# Connectors_GPIOs.net
KiCad netlist of a schematic drawn in Altium Designer
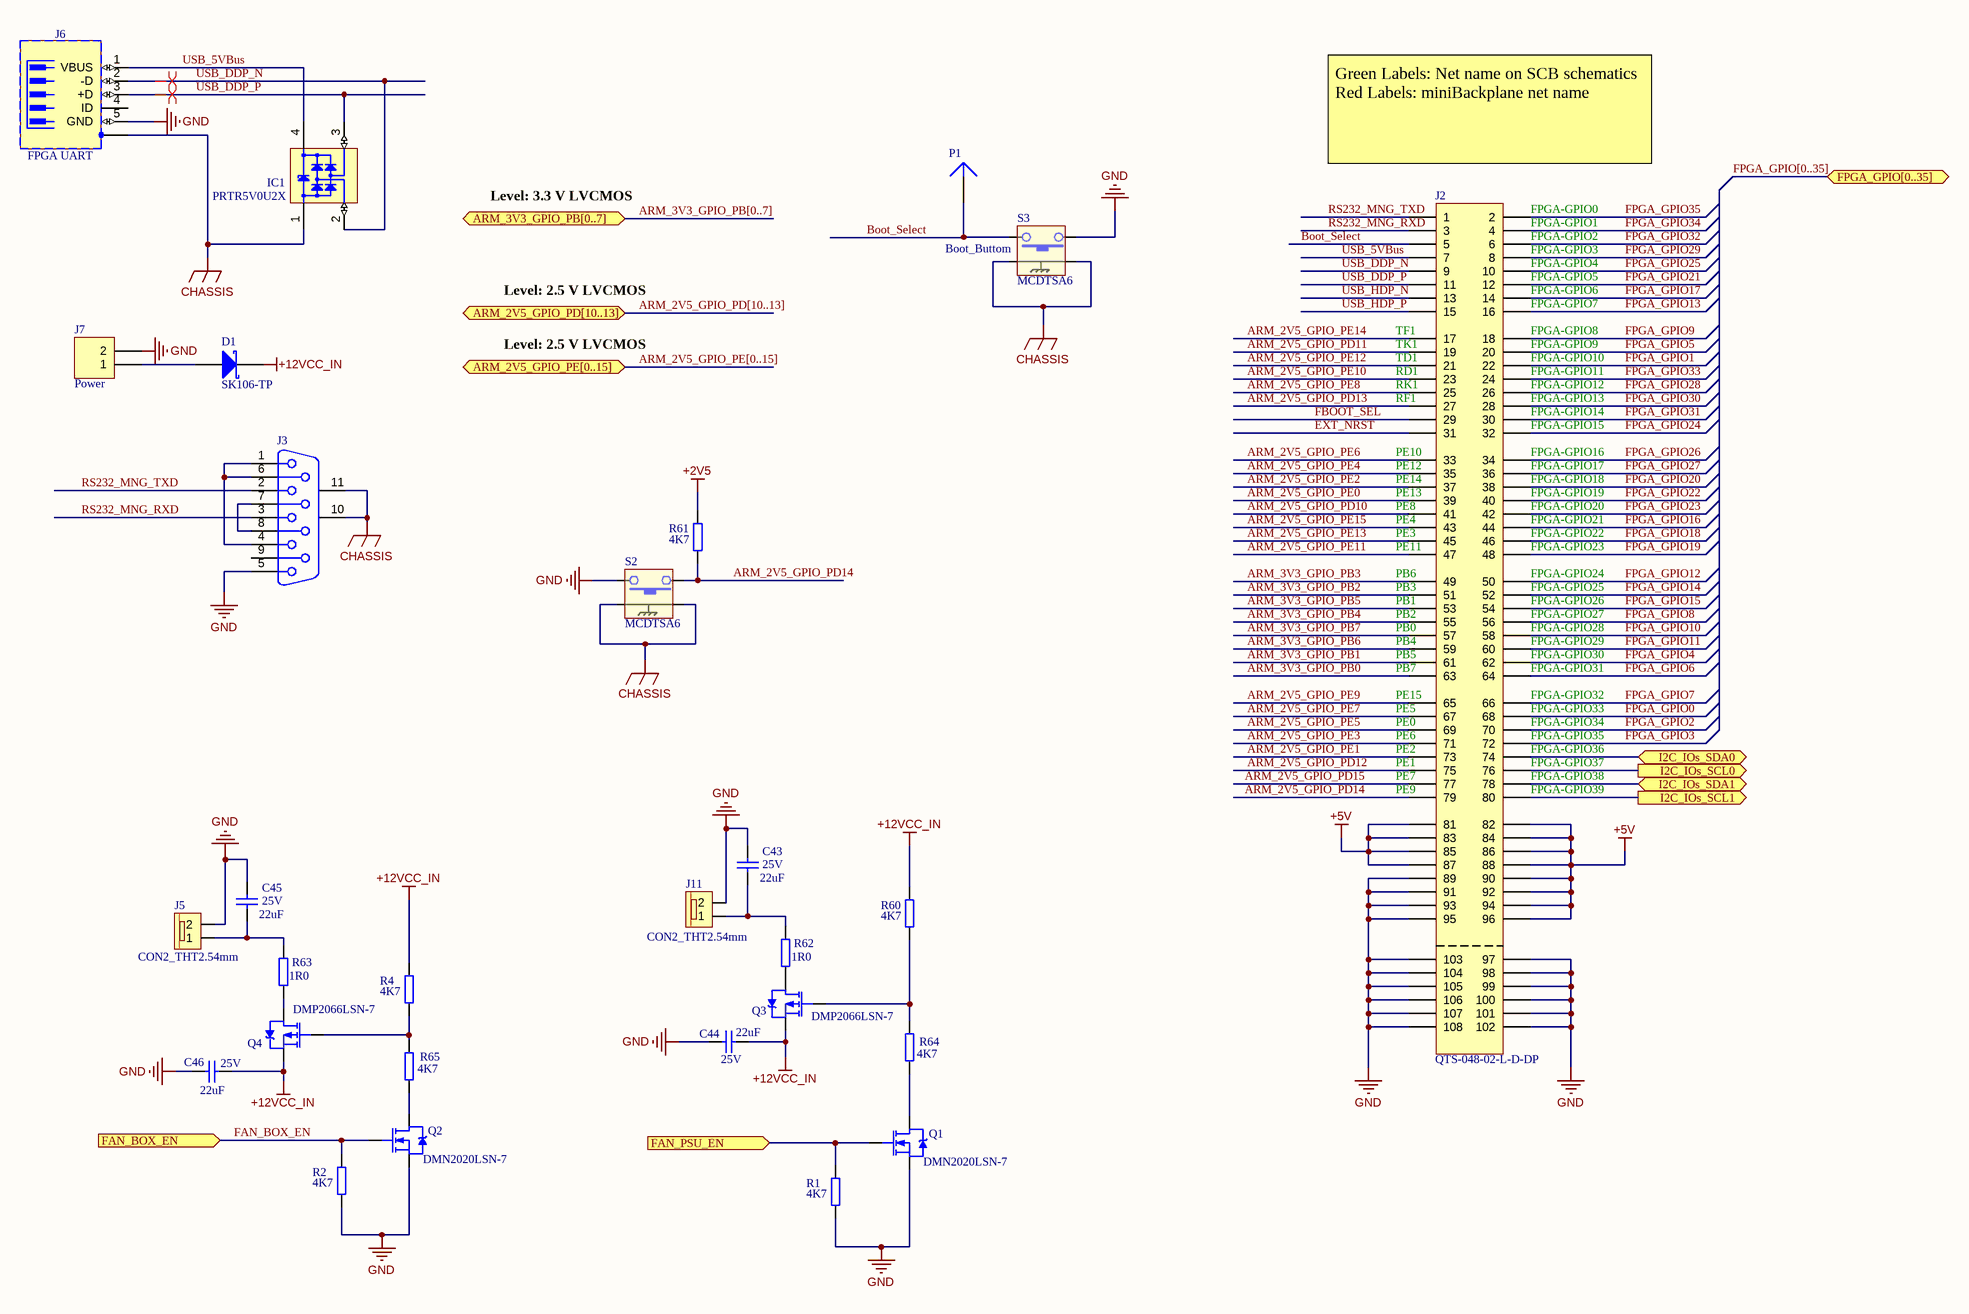
[diagram p0: Connectors_GPIOs.SchDoc]

(export (version "E")
  (design (tool "Eeschema 10.0.6"))
  (components
    (comp (ref "C43")
      (value "22uF")
      (footprint "CC3216-1206")
      (description "Capacitor")
      (fields
        (field (name "TOLERANCE") "±10%")
        (field (name "VOLTAGE") "25V")
        (field (name "Comment") "22uF 25V")
        (field (name "PUBLISHER") "Altium Limited")
      )
      (libsource (lib "wr_switch") (part "Cap"))
    )
    (comp (ref "C44")
      (value "22uF")
      (footprint "CC3216-1206")
      (description "Capacitor")
      (fields
        (field (name "TOLERANCE") "±10%")
        (field (name "VOLTAGE") "25V")
        (field (name "Comment") "22uF 25V")
        (field (name "PUBLISHER") "Altium Limited")
      )
      (libsource (lib "wr_switch") (part "Cap"))
    )
    (comp (ref "C45")
      (value "22uF")
      (footprint "CC3216-1206")
      (description "Capacitor")
      (fields
        (field (name "TOLERANCE") "±10%")
        (field (name "VOLTAGE") "25V")
        (field (name "Comment") "22uF 25V")
        (field (name "PUBLISHER") "Altium Limited")
      )
      (libsource (lib "wr_switch") (part "Cap"))
    )
    (comp (ref "C46")
      (value "22uF")
      (footprint "CC3216-1206")
      (description "Capacitor")
      (fields
        (field (name "TOLERANCE") "±10%")
        (field (name "VOLTAGE") "25V")
        (field (name "Comment") "22uF 25V")
        (field (name "PUBLISHER") "Altium Limited")
      )
      (libsource (lib "wr_switch") (part "Cap"))
    )
    (comp (ref "D1")
      (value "SK106-TP")
      (footprint "7S_WR:DO-214AB/SMB-MCC")
      (description "Schottky Diode 10A 60V")
      (libsource (lib "wr_switch") (part "SK106-TP"))
    )
    (comp (ref "IC1")
      (value "PRTR5V0U2X")
      (footprint "7S_WR:SOT190P230X110-4N")
      (description "Ultra Low Capacitance Double Rail-to-Rail ESD Protection Diode")
      (fields
        (field (name "VOLTAGE") "5.5V")
        (field (name "MANUFACTURER") "PHILIPS NXP")
        (field (name "AUTHOR") "CERN DEM JLC")
      )
      (libsource (lib "wr_switch") (part "PRTR5V0U2X"))
    )
    (comp (ref "J2")
      (value "QTS-048-02-L-D-DP")
      (footprint "QTS-048-XX-X-D-DP-A")
      (description "High Speed Ground Plane Header")
      (libsource (lib "wr_switch") (part "QTS-048-01-L-D-DP"))
    )
    (comp (ref "J3")
      (value "D Connector 9")
      (footprint "7S_WR:DSUB1.385-2H9")
      (description "Receptacle Assembly, 9 Position, Right Angle")
      (fields (field (name "PUBLISHER") "Altium Limited"))
      (libsource (lib "Miscellaneous Connectors") (part "D Connector 9"))
    )
    (comp (ref "J5")
      (value "CON2_THT2.54mm")
      (footprint "Wurth_619_0xx")
      (description "Connector")
      (libsource (lib "wr_switch") (part "CON2_619_0xx"))
    )
    (comp (ref "J6")
      (value "FPGA UART")
      (footprint "7S_WR:TYCO_1734035-1")
      (description "5 Pin + 1 Shield USB Receptacle")
      (fields
        (field (name "PART NUMBER") "TYCO_1734035-1")
        (field (name "MANUFACTURER") "TYCO ELECTRONICS")
        (field (name "AUTHOR") "CERN DEM JLC")
      )
      (libsource (lib "Connectors") (part "Connector USB 5 Pin + 1Shield"))
    )
    (comp (ref "J7")
      (value "Power")
      (footprint "7S_WR:TYCO_794120_1")
      (description "Header, 2-Pin")
      (fields (field (name "PUBLISHER") "Altium Limited"))
      (libsource (lib "Miscellaneous Connectors") (part "Header 2"))
    )
    (comp (ref "J11")
      (value "CON2_THT2.54mm")
      (footprint "Wurth_619_0xx")
      (description "Connector")
      (libsource (lib "wr_switch") (part "CON2_619_0xx"))
    )
    (comp (ref "P1")
      (value "Boot_Buttom")
      (footprint "PIN1-RT-01T-1.0B(LF)")
      (description "Plug")
      (fields (field (name "PUBLISHER") "Altium Limited"))
      (libsource (lib "Miscellaneous Connectors") (part "Plug"))
    )
    (comp (ref "Q1")
      (value "DMN2020LSN-7")
      (footprint "7S_WR:SC-59-3")
      (description "N-Channel Power MOSFET")
      (fields (field (name "MANUFACTURER") "Diodes Inc.") (field (name "PUBLISHER") "Altium Limited"))
      (libsource (lib "wr_switch") (part "NMOS-2"))
    )
    (comp (ref "Q2")
      (value "DMN2020LSN-7")
      (footprint "7S_WR:SC-59-3")
      (description "N-Channel Power MOSFET")
      (fields (field (name "MANUFACTURER") "Diodes Inc.") (field (name "PUBLISHER") "Altium Limited"))
      (libsource (lib "wr_switch") (part "NMOS-2"))
    )
    (comp (ref "Q3")
      (value "DMP2066LSN-7")
      (footprint "SC-59-3")
      (description "P-Channel Enhancement MOSFET")
      (fields (field (name "MANUFACTURER") "Diodes Inc."))
      (libsource (lib "wr_switch") (part "PMOS-2-Reflexion"))
    )
    (comp (ref "Q4")
      (value "DMP2066LSN-7")
      (footprint "SC-59-3")
      (description "P-Channel Enhancement MOSFET")
      (fields (field (name "MANUFACTURER") "Diodes Inc."))
      (libsource (lib "wr_switch") (part "PMOS-2-Reflexion"))
    )
    (comp (ref "R1")
      (value "4K7")
      (footprint "0603")
      (description "SMD Resistor")
      (fields (field (name "TOLERANCE") "±1%"))
      (libsource (lib "wr_switch") (part "RES_SMD"))
    )
    (comp (ref "R2")
      (value "4K7")
      (footprint "0603")
      (description "SMD Resistor")
      (fields (field (name "TOLERANCE") "±1%"))
      (libsource (lib "wr_switch") (part "RES_SMD"))
    )
    (comp (ref "R4")
      (value "4K7")
      (footprint "0603")
      (description "SMD Resistor")
      (fields (field (name "TOLERANCE") "±1%"))
      (libsource (lib "wr_switch") (part "RES_SMD"))
    )
    (comp (ref "R60")
      (value "4K7")
      (footprint "0603")
      (description "SMD Resistor")
      (fields (field (name "TOLERANCE") "±1%"))
      (libsource (lib "wr_switch") (part "RES_SMD"))
    )
    (comp (ref "R61")
      (value "4K7")
      (footprint "0603")
      (description "SMD Resistor")
      (fields (field (name "TOLERANCE") "±1%"))
      (libsource (lib "wr_switch") (part "RES_SMD"))
    )
    (comp (ref "R62")
      (value "1R0")
      (footprint "CR3225-1210")
      (description "SMD Resistor")
      (fields (field (name "TOLERANCE") "±1%"))
      (libsource (lib "wr_switch") (part "RES_SMD"))
    )
    (comp (ref "R63")
      (value "1R0")
      (footprint "CR3225-1210")
      (description "SMD Resistor")
      (fields (field (name "TOLERANCE") "±1%"))
      (libsource (lib "wr_switch") (part "RES_SMD"))
    )
    (comp (ref "R64")
      (value "4K7")
      (footprint "0603")
      (description "SMD Resistor")
      (fields (field (name "TOLERANCE") "±1%"))
      (libsource (lib "wr_switch") (part "RES_SMD"))
    )
    (comp (ref "R65")
      (value "4K7")
      (footprint "0603")
      (description "SMD Resistor")
      (fields (field (name "TOLERANCE") "±1%"))
      (libsource (lib "wr_switch") (part "RES_SMD"))
    )
    (comp (ref "S2")
      (value "MCDTSA6")
      (footprint "MCDTSA6")
      (description "Push button SPNO Right Angle Through Hole")
      (libsource (lib "wr_switch") (part "MCDTSA6"))
    )
    (comp (ref "S3")
      (value "MCDTSA6")
      (footprint "MCDTSA6")
      (description "Push button SPNO Right Angle Through Hole")
      (libsource (lib "wr_switch") (part "MCDTSA6"))
    )
  )
  (nets
    (net (code "1") (name "+2V5") (class "Default")
      (node (ref "R61") (pin "1") (pinfunction "1_1") (pintype "passive"))
    )
    (net (code "2") (name "+5V") (class "Default")
      (node (ref "J2") (pin "81") (pinfunction "81_81") (pintype "passive"))
      (node (ref "J2") (pin "82") (pinfunction "82_82") (pintype "passive"))
      (node (ref "J2") (pin "83") (pinfunction "83_83") (pintype "passive"))
      (node (ref "J2") (pin "84") (pinfunction "84_84") (pintype "passive"))
      (node (ref "J2") (pin "85") (pinfunction "85_85") (pintype "passive"))
      (node (ref "J2") (pin "86") (pinfunction "86_86") (pintype "passive"))
      (node (ref "J2") (pin "87") (pinfunction "87_87") (pintype "passive"))
      (node (ref "J2") (pin "88") (pinfunction "88_88") (pintype "passive"))
      (node (ref "J2") (pin "90") (pinfunction "90_90") (pintype "passive"))
      (node (ref "J2") (pin "92") (pinfunction "92_92") (pintype "passive"))
      (node (ref "J2") (pin "94") (pinfunction "94_94") (pintype "passive"))
      (node (ref "J2") (pin "96") (pinfunction "96_96") (pintype "passive"))
    )
    (net (code "3") (name "+12VCC_IN") (class "Default")
      (node (ref "C44") (pin "1") (pinfunction "1_1") (pintype "passive"))
      (node (ref "C46") (pin "1") (pinfunction "1_1") (pintype "passive"))
      (node (ref "D1") (pin "1") (pinfunction "K_1") (pintype "passive"))
      (node (ref "Q3") (pin "3") (pinfunction "S_3") (pintype "passive"))
      (node (ref "Q4") (pin "3") (pinfunction "S_3") (pintype "passive"))
      (node (ref "R4") (pin "1") (pinfunction "1_1") (pintype "passive"))
      (node (ref "R60") (pin "1") (pinfunction "1_1") (pintype "passive"))
    )
    (net (code "4") (name "/ARM_2V5_GPIO_PD10") (class "Default")
      (node (ref "J2") (pin "41") (pinfunction "41_41") (pintype "passive"))
    )
    (net (code "5") (name "/ARM_2V5_GPIO_PD11") (class "Default")
      (node (ref "J2") (pin "19") (pinfunction "19_19") (pintype "passive"))
    )
    (net (code "6") (name "/ARM_2V5_GPIO_PD12") (class "Default")
      (node (ref "J2") (pin "75") (pinfunction "75_75") (pintype "passive"))
    )
    (net (code "7") (name "/ARM_2V5_GPIO_PD13") (class "Default")
      (node (ref "J2") (pin "27") (pinfunction "27_27") (pintype "passive"))
    )
    (net (code "8") (name "/ARM_2V5_GPIO_PD14") (class "Default")
      (node (ref "J2") (pin "79") (pinfunction "79_79") (pintype "passive"))
      (node (ref "R61") (pin "2") (pinfunction "2_2") (pintype "passive"))
      (node (ref "S2") (pin "1") (pinfunction "1_1") (pintype "passive"))
    )
    (net (code "9") (name "/ARM_2V5_GPIO_PD15") (class "Default")
      (node (ref "J2") (pin "77") (pinfunction "77_77") (pintype "passive"))
    )
    (net (code "11") (name "/ARM_2V5_GPIO_PE0") (class "Default")
      (node (ref "J2") (pin "39") (pinfunction "39_39") (pintype "passive"))
    )
    (net (code "12") (name "/ARM_2V5_GPIO_PE1") (class "Default")
      (node (ref "J2") (pin "73") (pinfunction "73_73") (pintype "passive"))
    )
    (net (code "13") (name "/ARM_2V5_GPIO_PE2") (class "Default")
      (node (ref "J2") (pin "37") (pinfunction "37_37") (pintype "passive"))
    )
    (net (code "14") (name "/ARM_2V5_GPIO_PE3") (class "Default")
      (node (ref "J2") (pin "71") (pinfunction "71_71") (pintype "passive"))
    )
    (net (code "15") (name "/ARM_2V5_GPIO_PE4") (class "Default")
      (node (ref "J2") (pin "35") (pinfunction "35_35") (pintype "passive"))
    )
    (net (code "16") (name "/ARM_2V5_GPIO_PE5") (class "Default")
      (node (ref "J2") (pin "69") (pinfunction "69_69") (pintype "passive"))
    )
    (net (code "17") (name "/ARM_2V5_GPIO_PE6") (class "Default")
      (node (ref "J2") (pin "33") (pinfunction "33_33") (pintype "passive"))
    )
    (net (code "18") (name "/ARM_2V5_GPIO_PE7") (class "Default")
      (node (ref "J2") (pin "67") (pinfunction "67_67") (pintype "passive"))
    )
    (net (code "19") (name "/ARM_2V5_GPIO_PE8") (class "Default")
      (node (ref "J2") (pin "25") (pinfunction "25_25") (pintype "passive"))
    )
    (net (code "20") (name "/ARM_2V5_GPIO_PE9") (class "Default")
      (node (ref "J2") (pin "65") (pinfunction "65_65") (pintype "passive"))
    )
    (net (code "21") (name "/ARM_2V5_GPIO_PE10") (class "Default")
      (node (ref "J2") (pin "23") (pinfunction "23_23") (pintype "passive"))
    )
    (net (code "22") (name "/ARM_2V5_GPIO_PE11") (class "Default")
      (node (ref "J2") (pin "47") (pinfunction "47_47") (pintype "passive"))
    )
    (net (code "23") (name "/ARM_2V5_GPIO_PE12") (class "Default")
      (node (ref "J2") (pin "21") (pinfunction "21_21") (pintype "passive"))
    )
    (net (code "24") (name "/ARM_2V5_GPIO_PE13") (class "Default")
      (node (ref "J2") (pin "45") (pinfunction "45_45") (pintype "passive"))
    )
    (net (code "25") (name "/ARM_2V5_GPIO_PE14") (class "Default")
      (node (ref "J2") (pin "17") (pinfunction "17_17") (pintype "passive"))
    )
    (net (code "26") (name "/ARM_2V5_GPIO_PE15") (class "Default")
      (node (ref "J2") (pin "43") (pinfunction "43_43") (pintype "passive"))
    )
    (net (code "28") (name "/ARM_3V3_GPIO_PB0") (class "Default")
      (node (ref "J2") (pin "63") (pinfunction "63_63") (pintype "passive"))
    )
    (net (code "29") (name "/ARM_3V3_GPIO_PB1") (class "Default")
      (node (ref "J2") (pin "61") (pinfunction "61_61") (pintype "passive"))
    )
    (net (code "30") (name "/ARM_3V3_GPIO_PB2") (class "Default")
      (node (ref "J2") (pin "51") (pinfunction "51_51") (pintype "passive"))
    )
    (net (code "31") (name "/ARM_3V3_GPIO_PB3") (class "Default")
      (node (ref "J2") (pin "49") (pinfunction "49_49") (pintype "passive"))
    )
    (net (code "32") (name "/ARM_3V3_GPIO_PB4") (class "Default")
      (node (ref "J2") (pin "55") (pinfunction "55_55") (pintype "passive"))
    )
    (net (code "33") (name "/ARM_3V3_GPIO_PB5") (class "Default")
      (node (ref "J2") (pin "53") (pinfunction "53_53") (pintype "passive"))
    )
    (net (code "34") (name "/ARM_3V3_GPIO_PB6") (class "Default")
      (node (ref "J2") (pin "59") (pinfunction "59_59") (pintype "passive"))
    )
    (net (code "35") (name "/ARM_3V3_GPIO_PB7") (class "Default")
      (node (ref "J2") (pin "57") (pinfunction "57_57") (pintype "passive"))
    )
    (net (code "37") (name "/Boot_Select") (class "Default")
      (node (ref "J2") (pin "5") (pinfunction "5_5") (pintype "passive"))
      (node (ref "P1") (pin "1") (pinfunction "1_1") (pintype "passive"))
      (node (ref "S3") (pin "2") (pinfunction "2_2") (pintype "passive"))
    )
    (net (code "38") (name "/EXT_NRST") (class "Default")
      (node (ref "J2") (pin "31") (pinfunction "31_31") (pintype "passive"))
    )
    (net (code "39") (name "/FAN_BOX_EN") (class "Default")
      (node (ref "Q2") (pin "1") (pinfunction "G_1") (pintype "passive"))
      (node (ref "R2") (pin "1") (pinfunction "1_1") (pintype "passive"))
    )
    (net (code "40") (name "/FAN_PSU_EN") (class "Default")
      (node (ref "Q1") (pin "1") (pinfunction "G_1") (pintype "passive"))
      (node (ref "R1") (pin "1") (pinfunction "1_1") (pintype "passive"))
    )
    (net (code "41") (name "/FBOOT_SEL") (class "Default")
      (node (ref "J2") (pin "29") (pinfunction "29_29") (pintype "passive"))
    )
    (net (code "42") (name "/FPGA-GPIO36") (class "Default")
      (node (ref "J2") (pin "74") (pinfunction "74_74") (pintype "passive"))
    )
    (net (code "43") (name "/FPGA-GPIO37") (class "Default")
      (node (ref "J2") (pin "76") (pinfunction "76_76") (pintype "passive"))
    )
    (net (code "44") (name "/FPGA-GPIO38") (class "Default")
      (node (ref "J2") (pin "78") (pinfunction "78_78") (pintype "passive"))
    )
    (net (code "45") (name "/FPGA-GPIO39") (class "Default")
      (node (ref "J2") (pin "80") (pinfunction "80_80") (pintype "passive"))
    )
    (net (code "46") (name "/FPGA_GPIO0") (class "Default")
      (node (ref "J2") (pin "68") (pinfunction "68_68") (pintype "passive"))
    )
    (net (code "47") (name "/FPGA_GPIO1") (class "Default")
      (node (ref "J2") (pin "22") (pinfunction "22_22") (pintype "passive"))
    )
    (net (code "48") (name "/FPGA_GPIO2") (class "Default")
      (node (ref "J2") (pin "70") (pinfunction "70_70") (pintype "passive"))
    )
    (net (code "49") (name "/FPGA_GPIO3") (class "Default")
      (node (ref "J2") (pin "72") (pinfunction "72_72") (pintype "passive"))
    )
    (net (code "50") (name "/FPGA_GPIO4") (class "Default")
      (node (ref "J2") (pin "62") (pinfunction "62_62") (pintype "passive"))
    )
    (net (code "51") (name "/FPGA_GPIO5") (class "Default")
      (node (ref "J2") (pin "20") (pinfunction "20_20") (pintype "passive"))
    )
    (net (code "52") (name "/FPGA_GPIO6") (class "Default")
      (node (ref "J2") (pin "64") (pinfunction "64_64") (pintype "passive"))
    )
    (net (code "53") (name "/FPGA_GPIO7") (class "Default")
      (node (ref "J2") (pin "66") (pinfunction "66_66") (pintype "passive"))
    )
    (net (code "54") (name "/FPGA_GPIO8") (class "Default")
      (node (ref "J2") (pin "56") (pinfunction "56_56") (pintype "passive"))
    )
    (net (code "55") (name "/FPGA_GPIO9") (class "Default")
      (node (ref "J2") (pin "18") (pinfunction "18_18") (pintype "passive"))
    )
    (net (code "56") (name "/FPGA_GPIO10") (class "Default")
      (node (ref "J2") (pin "58") (pinfunction "58_58") (pintype "passive"))
    )
    (net (code "57") (name "/FPGA_GPIO11") (class "Default")
      (node (ref "J2") (pin "60") (pinfunction "60_60") (pintype "passive"))
    )
    (net (code "58") (name "/FPGA_GPIO12") (class "Default")
      (node (ref "J2") (pin "50") (pinfunction "50_50") (pintype "passive"))
    )
    (net (code "59") (name "/FPGA_GPIO13") (class "Default")
      (node (ref "J2") (pin "16") (pinfunction "16_16") (pintype "passive"))
    )
    (net (code "60") (name "/FPGA_GPIO14") (class "Default")
      (node (ref "J2") (pin "52") (pinfunction "52_52") (pintype "passive"))
    )
    (net (code "61") (name "/FPGA_GPIO15") (class "Default")
      (node (ref "J2") (pin "54") (pinfunction "54_54") (pintype "passive"))
    )
    (net (code "62") (name "/FPGA_GPIO16") (class "Default")
      (node (ref "J2") (pin "44") (pinfunction "44_44") (pintype "passive"))
    )
    (net (code "63") (name "/FPGA_GPIO17") (class "Default")
      (node (ref "J2") (pin "14") (pinfunction "14_14") (pintype "passive"))
    )
    (net (code "64") (name "/FPGA_GPIO18") (class "Default")
      (node (ref "J2") (pin "46") (pinfunction "46_46") (pintype "passive"))
    )
    (net (code "65") (name "/FPGA_GPIO19") (class "Default")
      (node (ref "J2") (pin "48") (pinfunction "48_48") (pintype "passive"))
    )
    (net (code "66") (name "/FPGA_GPIO20") (class "Default")
      (node (ref "J2") (pin "38") (pinfunction "38_38") (pintype "passive"))
    )
    (net (code "67") (name "/FPGA_GPIO21") (class "Default")
      (node (ref "J2") (pin "12") (pinfunction "12_12") (pintype "passive"))
    )
    (net (code "68") (name "/FPGA_GPIO22") (class "Default")
      (node (ref "J2") (pin "40") (pinfunction "40_40") (pintype "passive"))
    )
    (net (code "69") (name "/FPGA_GPIO23") (class "Default")
      (node (ref "J2") (pin "42") (pinfunction "42_42") (pintype "passive"))
    )
    (net (code "70") (name "/FPGA_GPIO24") (class "Default")
      (node (ref "J2") (pin "32") (pinfunction "32_32") (pintype "passive"))
    )
    (net (code "71") (name "/FPGA_GPIO25") (class "Default")
      (node (ref "J2") (pin "10") (pinfunction "10_10") (pintype "passive"))
    )
    (net (code "72") (name "/FPGA_GPIO26") (class "Default")
      (node (ref "J2") (pin "34") (pinfunction "34_34") (pintype "passive"))
    )
    (net (code "73") (name "/FPGA_GPIO27") (class "Default")
      (node (ref "J2") (pin "36") (pinfunction "36_36") (pintype "passive"))
    )
    (net (code "74") (name "/FPGA_GPIO28") (class "Default")
      (node (ref "J2") (pin "26") (pinfunction "26_26") (pintype "passive"))
    )
    (net (code "75") (name "/FPGA_GPIO29") (class "Default")
      (node (ref "J2") (pin "8") (pinfunction "8_8") (pintype "passive"))
    )
    (net (code "76") (name "/FPGA_GPIO30") (class "Default")
      (node (ref "J2") (pin "28") (pinfunction "28_28") (pintype "passive"))
    )
    (net (code "77") (name "/FPGA_GPIO31") (class "Default")
      (node (ref "J2") (pin "30") (pinfunction "30_30") (pintype "passive"))
    )
    (net (code "78") (name "/FPGA_GPIO32") (class "Default")
      (node (ref "J2") (pin "6") (pinfunction "6_6") (pintype "passive"))
    )
    (net (code "79") (name "/FPGA_GPIO33") (class "Default")
      (node (ref "J2") (pin "24") (pinfunction "24_24") (pintype "passive"))
    )
    (net (code "80") (name "/FPGA_GPIO34") (class "Default")
      (node (ref "J2") (pin "4") (pinfunction "4_4") (pintype "passive"))
    )
    (net (code "81") (name "/FPGA_GPIO35") (class "Default")
      (node (ref "J2") (pin "2") (pinfunction "2_2") (pintype "passive"))
    )
    (net (code "83") (name "/RS232_MNG_RXD") (class "Default")
      (node (ref "J2") (pin "3") (pinfunction "3_3") (pintype "passive"))
      (node (ref "J3") (pin "3") (pinfunction "3_3") (pintype "passive"))
    )
    (net (code "84") (name "/RS232_MNG_TXD") (class "Default")
      (node (ref "J2") (pin "1") (pinfunction "1_1") (pintype "passive"))
      (node (ref "J3") (pin "2") (pinfunction "2_2") (pintype "passive"))
    )
    (net (code "85") (name "/USB_5VBus") (class "Default")
      (node (ref "IC1") (pin "4") (pinfunction "VCC_4") (pintype "power_in"))
      (node (ref "J2") (pin "7") (pinfunction "7_7") (pintype "passive"))
      (node (ref "J6") (pin "1") (pinfunction "VBUS_1") (pintype "bidirectional"))
    )
    (net (code "86") (name "/USB_DDP_N") (class "Default")
      (node (ref "IC1") (pin "2") (pinfunction "I/O1_2") (pintype "bidirectional"))
      (node (ref "J2") (pin "9") (pinfunction "9_9") (pintype "passive"))
      (node (ref "J6") (pin "2") (pinfunction "-D_2") (pintype "bidirectional"))
    )
    (net (code "87") (name "/USB_DDP_P") (class "Default")
      (node (ref "IC1") (pin "3") (pinfunction "I/O2_3") (pintype "bidirectional"))
      (node (ref "J2") (pin "11") (pinfunction "11_11") (pintype "passive"))
      (node (ref "J6") (pin "3") (pinfunction "+D_3") (pintype "bidirectional"))
    )
    (net (code "88") (name "/USB_HDP_N") (class "Default")
      (node (ref "J2") (pin "13") (pinfunction "13_13") (pintype "passive"))
    )
    (net (code "89") (name "/USB_HDP_P") (class "Default")
      (node (ref "J2") (pin "15") (pinfunction "15_15") (pintype "passive"))
    )
    (net (code "90") (name "CHASSIS") (class "Default")
      (node (ref "IC1") (pin "1") (pinfunction "GND_1") (pintype "power_in"))
      (node (ref "J3") (pin "10") (pinfunction "MH1_10") (pintype "passive"))
      (node (ref "J3") (pin "11") (pinfunction "MH2_11") (pintype "passive"))
      (node (ref "J6") (pin "6") (pinfunction "SH_6") (pintype "power_in"))
      (node (ref "S2") (pin "3") (pinfunction "3_3") (pintype "power_in"))
      (node (ref "S2") (pin "4") (pinfunction "4_4") (pintype "power_in"))
      (node (ref "S3") (pin "3") (pinfunction "3_3") (pintype "power_in"))
      (node (ref "S3") (pin "4") (pinfunction "4_4") (pintype "power_in"))
    )
    (net (code "91") (name "GND") (class "Default")
      (node (ref "C43") (pin "2") (pinfunction "2_2") (pintype "passive"))
      (node (ref "C44") (pin "2") (pinfunction "2_2") (pintype "passive"))
      (node (ref "C45") (pin "2") (pinfunction "2_2") (pintype "passive"))
      (node (ref "C46") (pin "2") (pinfunction "2_2") (pintype "passive"))
      (node (ref "J11") (pin "2") (pinfunction "2_2") (pintype "passive"))
      (node (ref "J2") (pin "100") (pinfunction "100_100") (pintype "passive"))
      (node (ref "J2") (pin "101") (pinfunction "101_101") (pintype "passive"))
      (node (ref "J2") (pin "102") (pinfunction "102_102") (pintype "passive"))
      (node (ref "J2") (pin "103") (pinfunction "103_103") (pintype "passive"))
      (node (ref "J2") (pin "104") (pinfunction "104_104") (pintype "passive"))
      (node (ref "J2") (pin "105") (pinfunction "105_105") (pintype "passive"))
      (node (ref "J2") (pin "106") (pinfunction "106_106") (pintype "passive"))
      (node (ref "J2") (pin "107") (pinfunction "107_107") (pintype "passive"))
      (node (ref "J2") (pin "108") (pinfunction "108_108") (pintype "passive"))
      (node (ref "J2") (pin "89") (pinfunction "89_89") (pintype "passive"))
      (node (ref "J2") (pin "91") (pinfunction "91_91") (pintype "passive"))
      (node (ref "J2") (pin "93") (pinfunction "93_93") (pintype "passive"))
      (node (ref "J2") (pin "95") (pinfunction "95_95") (pintype "passive"))
      (node (ref "J2") (pin "97") (pinfunction "97_97") (pintype "passive"))
      (node (ref "J2") (pin "98") (pinfunction "98_98") (pintype "passive"))
      (node (ref "J2") (pin "99") (pinfunction "99_99") (pintype "passive"))
      (node (ref "J3") (pin "5") (pinfunction "5_5") (pintype "passive"))
      (node (ref "J5") (pin "2") (pinfunction "2_2") (pintype "passive"))
      (node (ref "J6") (pin "5") (pinfunction "GND_5") (pintype "bidirectional"))
      (node (ref "J7") (pin "2") (pinfunction "2_2") (pintype "passive"))
      (node (ref "Q1") (pin "3") (pinfunction "S_3") (pintype "passive"))
      (node (ref "Q2") (pin "3") (pinfunction "S_3") (pintype "passive"))
      (node (ref "R1") (pin "2") (pinfunction "2_2") (pintype "passive"))
      (node (ref "R2") (pin "2") (pinfunction "2_2") (pintype "passive"))
      (node (ref "S2") (pin "2") (pinfunction "2_2") (pintype "passive"))
      (node (ref "S3") (pin "1") (pinfunction "1_1") (pintype "passive"))
    )
    (net (code "92") (name "Net-(C43-Pad1)") (class "Default")
      (node (ref "C43") (pin "1") (pinfunction "1_1") (pintype "passive"))
      (node (ref "J11") (pin "1") (pinfunction "1_1") (pintype "passive"))
      (node (ref "R62") (pin "2") (pinfunction "2_2") (pintype "passive"))
    )
    (net (code "93") (name "Net-(C45-Pad1)") (class "Default")
      (node (ref "C45") (pin "1") (pinfunction "1_1") (pintype "passive"))
      (node (ref "J5") (pin "1") (pinfunction "1_1") (pintype "passive"))
      (node (ref "R63") (pin "2") (pinfunction "2_2") (pintype "passive"))
    )
    (net (code "94") (name "Net-(D1-A)") (class "Default")
      (node (ref "D1") (pin "2") (pinfunction "A_2") (pintype "passive"))
      (node (ref "J7") (pin "1") (pinfunction "1_1") (pintype "passive"))
    )
    (net (code "95") (name "Net-(J3-Pad1)") (class "Default")
      (node (ref "J3") (pin "1") (pinfunction "1_1") (pintype "passive"))
      (node (ref "J3") (pin "4") (pinfunction "4_4") (pintype "passive"))
      (node (ref "J3") (pin "6") (pinfunction "6_6") (pintype "passive"))
    )
    (net (code "96") (name "Net-(J3-Pad7)") (class "Default")
      (node (ref "J3") (pin "7") (pinfunction "7_7") (pintype "passive"))
      (node (ref "J3") (pin "8") (pinfunction "8_8") (pintype "passive"))
    )
    (net (code "97") (name "Net-(Q1-D)") (class "Default")
      (node (ref "Q1") (pin "2") (pinfunction "D_2") (pintype "passive"))
      (node (ref "R64") (pin "2") (pinfunction "2_2") (pintype "passive"))
    )
    (net (code "98") (name "Net-(Q2-D)") (class "Default")
      (node (ref "Q2") (pin "2") (pinfunction "D_2") (pintype "passive"))
      (node (ref "R65") (pin "2") (pinfunction "2_2") (pintype "passive"))
    )
    (net (code "99") (name "Net-(Q3-D)") (class "Default")
      (node (ref "Q3") (pin "2") (pinfunction "D_2") (pintype "passive"))
      (node (ref "R62") (pin "1") (pinfunction "1_1") (pintype "passive"))
    )
    (net (code "100") (name "Net-(Q3-G)") (class "Default")
      (node (ref "Q3") (pin "1") (pinfunction "G_1") (pintype "passive"))
      (node (ref "R60") (pin "2") (pinfunction "2_2") (pintype "passive"))
      (node (ref "R64") (pin "1") (pinfunction "1_1") (pintype "passive"))
    )
    (net (code "101") (name "Net-(Q4-D)") (class "Default")
      (node (ref "Q4") (pin "2") (pinfunction "D_2") (pintype "passive"))
      (node (ref "R63") (pin "1") (pinfunction "1_1") (pintype "passive"))
    )
    (net (code "102") (name "Net-(Q4-G)") (class "Default")
      (node (ref "Q4") (pin "1") (pinfunction "G_1") (pintype "passive"))
      (node (ref "R4") (pin "2") (pinfunction "2_2") (pintype "passive"))
      (node (ref "R65") (pin "1") (pinfunction "1_1") (pintype "passive"))
    )
    (net (code "103") (name "unconnected-(J3-Pad9)") (class "Default")
      (node (ref "J3") (pin "9") (pinfunction "9_9") (pintype "passive"))
    )
    (net (code "104") (name "unconnected-(J6-ID-Pad4)") (class "Default")
      (node (ref "J6") (pin "4") (pinfunction "ID_4") (pintype "passive"))
    )
  )
)
